# Tayloe_Detector_v5.net
KiCad netlist of a schematic drawn in EAGLE
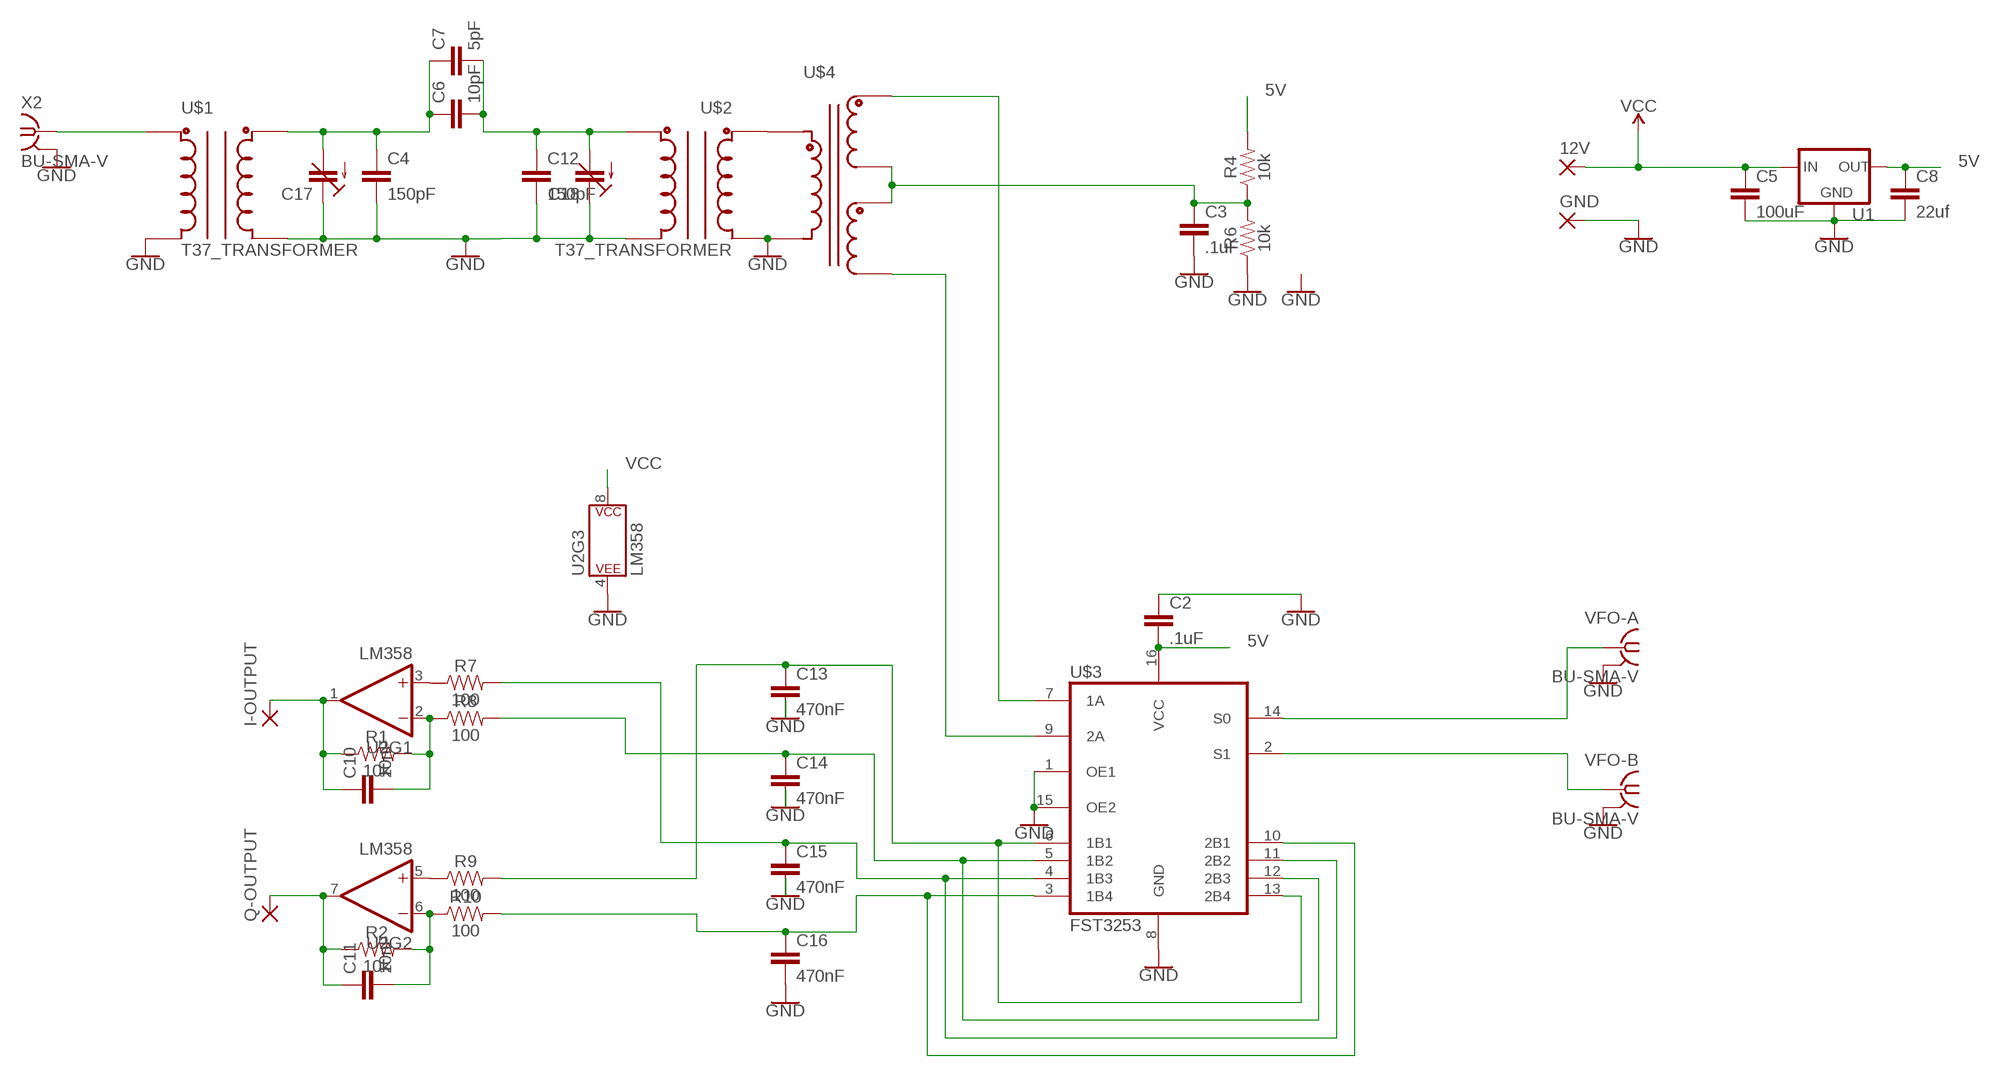
[diagram p0: schematic, sheet 1]

(export (version "E")
  (design (tool "Eeschema 10.0.6"))
  (components
    (comp (ref "12V")
      (value "3,17/1,1")
      (footprint "eagle-import:3,17_1,1")
      (libsource (lib "eagle-import") (part "3,17/1,1"))
    )
    (comp (ref "C2")
      (value ".1uF")
      (footprint "eagle-import:C5B3.5")
      (libsource (lib "eagle-import") (part "C5/3.5"))
    )
    (comp (ref "C3")
      (value ".1uF")
      (footprint "eagle-import:C5B3.5")
      (libsource (lib "eagle-import") (part "C5/3.5"))
    )
    (comp (ref "C4")
      (value "150pF")
      (footprint "eagle-import:C5B3.5")
      (libsource (lib "eagle-import") (part "C5/3.5"))
    )
    (comp (ref "C5")
      (value "100uF")
      (footprint "eagle-import:C5B3.5")
      (libsource (lib "eagle-import") (part "C5/3.5"))
    )
    (comp (ref "C6")
      (value "10pF")
      (footprint "eagle-import:C5B3.5")
      (libsource (lib "eagle-import") (part "C5/3.5"))
    )
    (comp (ref "C7")
      (value "5pF")
      (footprint "eagle-import:C5B3.5")
      (libsource (lib "eagle-import") (part "C5/3.5"))
    )
    (comp (ref "C8")
      (value "22uf")
      (footprint "eagle-import:C5B3.5")
      (libsource (lib "eagle-import") (part "C5/3.5"))
    )
    (comp (ref "C10")
      (value "10nF")
      (footprint "eagle-import:C5B3.5")
      (libsource (lib "eagle-import") (part "C5/3.5"))
    )
    (comp (ref "C11")
      (value "10nF")
      (footprint "eagle-import:C5B3.5")
      (libsource (lib "eagle-import") (part "C5/3.5"))
    )
    (comp (ref "C12")
      (value "150pF")
      (footprint "eagle-import:C5B3.5")
      (libsource (lib "eagle-import") (part "C5/3.5"))
    )
    (comp (ref "C13")
      (value "470nF")
      (footprint "eagle-import:C5B3.5")
      (libsource (lib "eagle-import") (part "C5/3.5"))
    )
    (comp (ref "C14")
      (value "470nF")
      (footprint "eagle-import:C5B3.5")
      (libsource (lib "eagle-import") (part "C5/3.5"))
    )
    (comp (ref "C15")
      (value "470nF")
      (footprint "eagle-import:C5B3.5")
      (libsource (lib "eagle-import") (part "C5/3.5"))
    )
    (comp (ref "C16")
      (value "470nF")
      (footprint "eagle-import:C5B3.5")
      (libsource (lib "eagle-import") (part "C5/3.5"))
    )
    (comp (ref "C17")
      (value "C-TRIMMTZ03")
      (footprint "eagle-import:CTRIMTZ03")
      (libsource (lib "eagle-import") (part "C-TRIMMTZ03"))
    )
    (comp (ref "C18")
      (value "C-TRIMMTZ03")
      (footprint "eagle-import:CTRIMTZ03")
      (libsource (lib "eagle-import") (part "C-TRIMMTZ03"))
    )
    (comp (ref "GND")
      (value "3,17/1,1")
      (footprint "eagle-import:3,17_1,1")
      (libsource (lib "eagle-import") (part "3,17/1,1"))
    )
    (comp (ref "I-OUTPUT")
      (value "3,17/1,1")
      (footprint "eagle-import:3,17_1,1")
      (libsource (lib "eagle-import") (part "3,17/1,1"))
    )
    (comp (ref "Q-OUTPUT")
      (value "3,17/1,1")
      (footprint "eagle-import:3,17_1,1")
      (libsource (lib "eagle-import") (part "3,17/1,1"))
    )
    (comp (ref "R1")
      (value "10k")
      (footprint "eagle-import:AXIAL-0.3")
      (libsource (lib "eagle-import") (part "1KOHM-HORIZ-1/4W-1%"))
    )
    (comp (ref "R2")
      (value "10k")
      (footprint "eagle-import:AXIAL-0.3")
      (libsource (lib "eagle-import") (part "1KOHM-HORIZ-1/4W-1%"))
    )
    (comp (ref "R4")
      (value "10k")
      (footprint "eagle-import:AXIAL-0.3")
      (libsource (lib "eagle-import") (part "1KOHM-HORIZ-1/4W-1%"))
    )
    (comp (ref "R6")
      (value "10k")
      (footprint "eagle-import:AXIAL-0.3")
      (libsource (lib "eagle-import") (part "1KOHM-HORIZ-1/4W-1%"))
    )
    (comp (ref "R7")
      (value "100")
      (footprint "eagle-import:AXIAL-0.3")
      (libsource (lib "eagle-import") (part "1KOHM-HORIZ-1/4W-1%"))
    )
    (comp (ref "R8")
      (value "100")
      (footprint "eagle-import:AXIAL-0.3")
      (libsource (lib "eagle-import") (part "1KOHM-HORIZ-1/4W-1%"))
    )
    (comp (ref "R9")
      (value "100")
      (footprint "eagle-import:AXIAL-0.3")
      (libsource (lib "eagle-import") (part "1KOHM-HORIZ-1/4W-1%"))
    )
    (comp (ref "R10")
      (value "100")
      (footprint "eagle-import:AXIAL-0.3")
      (libsource (lib "eagle-import") (part "1KOHM-HORIZ-1/4W-1%"))
    )
    (comp (ref "U$1")
      (value "T37_TRANSFORMER")
      (footprint "eagle-import:T37_TRANSFORMER")
      (libsource (lib "eagle-import") (part "T37_TRANSFORMER"))
    )
    (comp (ref "U$2")
      (value "T37_TRANSFORMER")
      (footprint "eagle-import:T37_TRANSFORMER")
      (libsource (lib "eagle-import") (part "T37_TRANSFORMER"))
    )
    (comp (ref "U$3")
      (value "FST3253")
      (footprint "eagle-import:SO16")
      (libsource (lib "eagle-import") (part "FST3253"))
    )
    (comp (ref "U$4")
      (value "T50_SPLITTER")
      (footprint "eagle-import:T50_SPLITTER")
      (libsource (lib "eagle-import") (part "T50_SPLITTER"))
    )
    (comp (ref "U1")
      (value "V_REG_78XXTO-92_UNTESTED")
      (footprint "eagle-import:TO-92")
      (libsource (lib "eagle-import") (part "V_REG_78XXTO-92_UNTESTED"))
    )
    (comp (ref "U2")
      (value "LM358")
      (footprint "eagle-import:DIP08")
      (libsource (lib "eagle-import") (part "LM358"))
    )
    (comp (ref "VFO-A")
      (value "BU-SMA-V")
      (footprint "eagle-import:BU-SMA-V")
      (libsource (lib "eagle-import") (part "BU-SMA-V"))
    )
    (comp (ref "VFO-B")
      (value "BU-SMA-V")
      (footprint "eagle-import:BU-SMA-V")
      (libsource (lib "eagle-import") (part "BU-SMA-V"))
    )
    (comp (ref "X2")
      (value "BU-SMA-V")
      (footprint "eagle-import:BU-SMA-V")
      (libsource (lib "eagle-import") (part "BU-SMA-V"))
    )
  )
  (nets
    (net (code "1") (name "/5V") (class "Default")
      (node (ref "C2") (pin "2") (pinfunction "2_2") (pintype "passive"))
      (node (ref "C8") (pin "1") (pinfunction "1_1") (pintype "passive"))
      (node (ref "R4") (pin "P$2") (pinfunction "2_P$2") (pintype "passive"))
      (node (ref "U$3") (pin "16") (pinfunction "VCC_16") (pintype "bidirectional"))
      (node (ref "U1") (pin "1") (pinfunction "OUT_1") (pintype "passive"))
    )
    (net (code "2") (name "GND") (class "Default")
      (node (ref "C12") (pin "2") (pinfunction "2_2") (pintype "passive"))
      (node (ref "C13") (pin "2") (pinfunction "2_2") (pintype "passive"))
      (node (ref "C14") (pin "2") (pinfunction "2_2") (pintype "passive"))
      (node (ref "C15") (pin "2") (pinfunction "2_2") (pintype "passive"))
      (node (ref "C16") (pin "2") (pinfunction "2_2") (pintype "passive"))
      (node (ref "C17") (pin "1") (pinfunction "E_1") (pintype "passive"))
      (node (ref "C18") (pin "1") (pinfunction "E_1") (pintype "passive"))
      (node (ref "C2") (pin "1") (pinfunction "1_1") (pintype "passive"))
      (node (ref "C3") (pin "2") (pinfunction "2_2") (pintype "passive"))
      (node (ref "C4") (pin "2") (pinfunction "2_2") (pintype "passive"))
      (node (ref "C5") (pin "2") (pinfunction "2_2") (pintype "passive"))
      (node (ref "C8") (pin "2") (pinfunction "2_2") (pintype "passive"))
      (node (ref "GND") (pin "1") (pinfunction "P_1") (pintype "passive"))
      (node (ref "R6") (pin "P$1") (pinfunction "1_P$1") (pintype "passive"))
      (node (ref "U$1") (pin "C1A") (pinfunction "C1A_C1A") (pintype "bidirectional"))
      (node (ref "U$1") (pin "C2A") (pinfunction "C2A_C2A") (pintype "bidirectional"))
      (node (ref "U$2") (pin "C1A") (pinfunction "C1A_C1A") (pintype "bidirectional"))
      (node (ref "U$2") (pin "C2A") (pinfunction "C2A_C2A") (pintype "bidirectional"))
      (node (ref "U$3") (pin "1") (pinfunction "OE1_1") (pintype "bidirectional"))
      (node (ref "U$3") (pin "15") (pinfunction "OE2_15") (pintype "bidirectional"))
      (node (ref "U$3") (pin "8") (pinfunction "GND_8") (pintype "bidirectional"))
      (node (ref "U$4") (pin "C1A") (pinfunction "C1A_C1A") (pintype "bidirectional"))
      (node (ref "U1") (pin "2") (pinfunction "GND_2") (pintype "input"))
      (node (ref "U2") (pin "4") (pinfunction "P$V-_4") (pintype "bidirectional"))
      (node (ref "VFO-A") (pin "2") (pinfunction "2_2") (pintype "passive"))
      (node (ref "VFO-A") (pin "3") (pinfunction "2_3") (pintype "passive"))
      (node (ref "VFO-A") (pin "4") (pinfunction "2_4") (pintype "passive"))
      (node (ref "VFO-A") (pin "5") (pinfunction "2_5") (pintype "passive"))
      (node (ref "VFO-B") (pin "2") (pinfunction "2_2") (pintype "passive"))
      (node (ref "VFO-B") (pin "3") (pinfunction "2_3") (pintype "passive"))
      (node (ref "VFO-B") (pin "4") (pinfunction "2_4") (pintype "passive"))
      (node (ref "VFO-B") (pin "5") (pinfunction "2_5") (pintype "passive"))
      (node (ref "X2") (pin "2") (pinfunction "2_2") (pintype "passive"))
      (node (ref "X2") (pin "3") (pinfunction "2_3") (pintype "passive"))
      (node (ref "X2") (pin "4") (pinfunction "2_4") (pintype "passive"))
      (node (ref "X2") (pin "5") (pinfunction "2_5") (pintype "passive"))
    )
    (net (code "3") (name "Net-(C17-A)") (class "Default")
      (node (ref "C17") (pin "2") (pinfunction "A_2") (pintype "passive"))
      (node (ref "C4") (pin "1") (pinfunction "1_1") (pintype "passive"))
      (node (ref "C6") (pin "1") (pinfunction "1_1") (pintype "passive"))
      (node (ref "C7") (pin "1") (pinfunction "1_1") (pintype "passive"))
      (node (ref "U$1") (pin "C2B") (pinfunction "C2B_C2B") (pintype "bidirectional"))
    )
    (net (code "4") (name "Net-(C18-A)") (class "Default")
      (node (ref "C12") (pin "1") (pinfunction "1_1") (pintype "passive"))
      (node (ref "C18") (pin "2") (pinfunction "A_2") (pintype "passive"))
      (node (ref "C6") (pin "2") (pinfunction "2_2") (pintype "passive"))
      (node (ref "C7") (pin "2") (pinfunction "2_2") (pintype "passive"))
      (node (ref "U$2") (pin "C2B") (pinfunction "C2B_C2B") (pintype "bidirectional"))
    )
    (net (code "5") (name "Net-(I-OUTPUT-P)") (class "Default")
      (node (ref "C10") (pin "1") (pinfunction "1_1") (pintype "passive"))
      (node (ref "I-OUTPUT") (pin "1") (pinfunction "P_1") (pintype "passive"))
      (node (ref "R1") (pin "P$1") (pinfunction "1_P$1") (pintype "passive"))
      (node (ref "U2") (pin "1") (pinfunction "OUT_1") (pintype "output"))
    )
    (net (code "6") (name "Net-(Q-OUTPUT-P)") (class "Default")
      (node (ref "C11") (pin "1") (pinfunction "1_1") (pintype "passive"))
      (node (ref "Q-OUTPUT") (pin "1") (pinfunction "P_1") (pintype "passive"))
      (node (ref "R2") (pin "P$1") (pinfunction "1_P$1") (pintype "passive"))
      (node (ref "U2") (pin "7") (pinfunction "OUT_7") (pintype "output"))
    )
    (net (code "7") (name "Net-(R1-2)") (class "Default")
      (node (ref "C10") (pin "2") (pinfunction "2_2") (pintype "passive"))
      (node (ref "R1") (pin "P$2") (pinfunction "2_P$2") (pintype "passive"))
      (node (ref "R8") (pin "P$1") (pinfunction "1_P$1") (pintype "passive"))
      (node (ref "U2") (pin "2") (pinfunction "-IN_2") (pintype "input"))
    )
    (net (code "8") (name "Net-(R4-1)") (class "Default")
      (node (ref "C3") (pin "1") (pinfunction "1_1") (pintype "passive"))
      (node (ref "R4") (pin "P$1") (pinfunction "1_P$1") (pintype "passive"))
      (node (ref "R6") (pin "P$2") (pinfunction "2_P$2") (pintype "passive"))
      (node (ref "U$4") (pin "C2A") (pinfunction "C3B_C2A") (pintype "bidirectional"))
      (node (ref "U$4") (pin "C3A") (pinfunction "C2A_C3A") (pintype "bidirectional"))
    )
    (net (code "9") (name "Net-(R7-1)") (class "Default")
      (node (ref "R7") (pin "P$1") (pinfunction "1_P$1") (pintype "passive"))
      (node (ref "U2") (pin "3") (pinfunction "+IN_3") (pintype "input"))
    )
    (net (code "10") (name "Net-(R7-2)") (class "Default")
      (node (ref "C15") (pin "1") (pinfunction "1_1") (pintype "passive"))
      (node (ref "R7") (pin "P$2") (pinfunction "2_P$2") (pintype "passive"))
      (node (ref "U$3") (pin "11") (pinfunction "2B2_11") (pintype "output"))
      (node (ref "U$3") (pin "4") (pinfunction "1B3_4") (pintype "output"))
    )
    (net (code "11") (name "Net-(R8-2)") (class "Default")
      (node (ref "C14") (pin "1") (pinfunction "1_1") (pintype "passive"))
      (node (ref "R8") (pin "P$2") (pinfunction "2_P$2") (pintype "passive"))
      (node (ref "U$3") (pin "12") (pinfunction "2B3_12") (pintype "input"))
      (node (ref "U$3") (pin "5") (pinfunction "1B2_5") (pintype "input"))
    )
    (net (code "12") (name "Net-(R9-1)") (class "Default")
      (node (ref "R9") (pin "P$1") (pinfunction "1_P$1") (pintype "passive"))
      (node (ref "U2") (pin "5") (pinfunction "+IN_5") (pintype "input"))
    )
    (net (code "13") (name "Net-(R9-2)") (class "Default")
      (node (ref "C13") (pin "1") (pinfunction "1_1") (pintype "passive"))
      (node (ref "R9") (pin "P$2") (pinfunction "2_P$2") (pintype "passive"))
      (node (ref "U$3") (pin "13") (pinfunction "2B4_13") (pintype "input"))
      (node (ref "U$3") (pin "6") (pinfunction "1B1_6") (pintype "input"))
    )
    (net (code "14") (name "Net-(R10-1)") (class "Default")
      (node (ref "C11") (pin "2") (pinfunction "2_2") (pintype "passive"))
      (node (ref "R10") (pin "P$1") (pinfunction "1_P$1") (pintype "passive"))
      (node (ref "R2") (pin "P$2") (pinfunction "2_P$2") (pintype "passive"))
      (node (ref "U2") (pin "6") (pinfunction "-IN_6") (pintype "input"))
    )
    (net (code "15") (name "Net-(R10-2)") (class "Default")
      (node (ref "C16") (pin "1") (pinfunction "1_1") (pintype "passive"))
      (node (ref "R10") (pin "P$2") (pinfunction "2_P$2") (pintype "passive"))
      (node (ref "U$3") (pin "10") (pinfunction "2B1_10") (pintype "output"))
      (node (ref "U$3") (pin "3") (pinfunction "1B4_3") (pintype "output"))
    )
    (net (code "16") (name "Net-(U$1-PadC1B)") (class "Default")
      (node (ref "U$1") (pin "C1B") (pinfunction "C1B_C1B") (pintype "bidirectional"))
      (node (ref "X2") (pin "1") (pinfunction "1_1") (pintype "passive"))
    )
    (net (code "17") (name "Net-(U$2-PadC1B)") (class "Default")
      (node (ref "U$2") (pin "C1B") (pinfunction "C1B_C1B") (pintype "bidirectional"))
      (node (ref "U$4") (pin "C1B") (pinfunction "C1B_C1B") (pintype "bidirectional"))
    )
    (net (code "18") (name "Net-(U$3-1A)") (class "Default")
      (node (ref "U$3") (pin "7") (pinfunction "1A_7") (pintype "bidirectional"))
      (node (ref "U$4") (pin "C3B") (pinfunction "C2B_C3B") (pintype "bidirectional"))
    )
    (net (code "19") (name "Net-(U$3-2A)") (class "Default")
      (node (ref "U$3") (pin "9") (pinfunction "2A_9") (pintype "bidirectional"))
      (node (ref "U$4") (pin "C2B") (pinfunction "C3A_C2B") (pintype "bidirectional"))
    )
    (net (code "20") (name "Net-(U$3-S0)") (class "Default")
      (node (ref "U$3") (pin "14") (pinfunction "S0_14") (pintype "bidirectional"))
      (node (ref "VFO-A") (pin "1") (pinfunction "1_1") (pintype "passive"))
    )
    (net (code "21") (name "Net-(U$3-S1)") (class "Default")
      (node (ref "U$3") (pin "2") (pinfunction "S1_2") (pintype "bidirectional"))
      (node (ref "VFO-B") (pin "1") (pinfunction "1_1") (pintype "passive"))
    )
    (net (code "22") (name "VCC") (class "Default")
      (node (ref "12V") (pin "1") (pinfunction "P_1") (pintype "passive"))
      (node (ref "C5") (pin "1") (pinfunction "1_1") (pintype "passive"))
      (node (ref "U1") (pin "3") (pinfunction "IN_3") (pintype "input"))
      (node (ref "U2") (pin "8") (pinfunction "P$V+_8") (pintype "bidirectional"))
    )
  )
)
